# schema.net
KiCad netlist of a schematic drawn in EAGLE
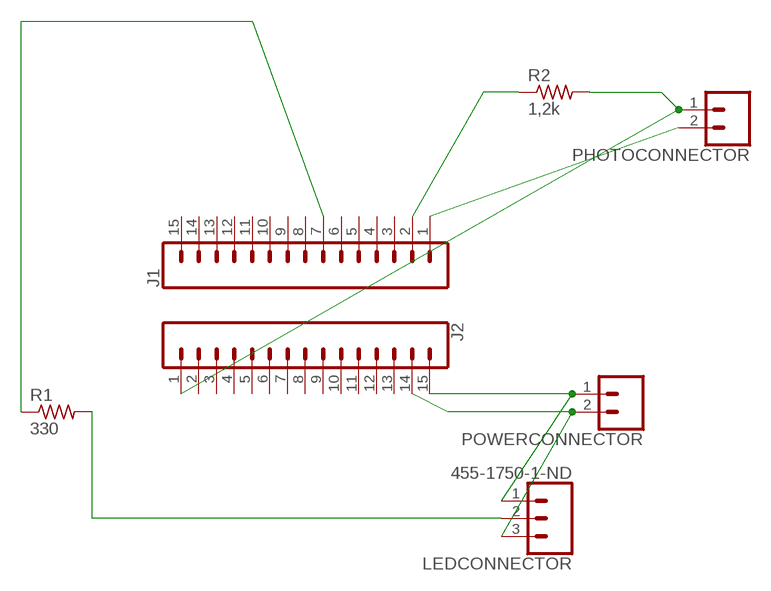
[diagram p0: schematic, sheet 1]

(export (version "E")
  (design (tool "Eeschema 10.0.6"))
  (components
    (comp (ref "J1")
      (value "CONN_15")
      (footprint "eagle-import:1X15")
      (libsource (lib "eagle-import") (part "CONN_15"))
    )
    (comp (ref "J2")
      (value "CONN_15")
      (footprint "eagle-import:1X15")
      (libsource (lib "eagle-import") (part "CONN_15"))
    )
    (comp (ref "LEDCONNECTOR")
      (value "455-1750-1-ND")
      (footprint "eagle-import:1X03")
      (libsource (lib "eagle-import") (part "CONN_03"))
    )
    (comp (ref "PHOTOCONNECTOR")
      (value "CONN_02")
      (footprint "eagle-import:1X02")
      (libsource (lib "eagle-import") (part "CONN_02"))
    )
    (comp (ref "POWERCONNECTOR")
      (value "CONN_02")
      (footprint "eagle-import:1X02")
      (libsource (lib "eagle-import") (part "CONN_02"))
    )
    (comp (ref "R1")
      (value "330")
      (footprint "eagle-import:0204V")
      (libsource (lib "eagle-import") (part "R-US_0204/2V"))
    )
    (comp (ref "R2")
      (value "1,2k")
      (footprint "eagle-import:0204V")
      (libsource (lib "eagle-import") (part "R-US_0204/2V"))
    )
  )
  (nets
    (net (code "1") (name "Net-(J1-Pad1)") (class "Default")
      (node (ref "J1") (pin "1") (pinfunction "1_1") (pintype "passive"))
      (node (ref "PHOTOCONNECTOR") (pin "2") (pinfunction "2_2") (pintype "passive"))
    )
    (net (code "2") (name "Net-(J1-Pad2)") (class "Default")
      (node (ref "J1") (pin "2") (pinfunction "2_2") (pintype "passive"))
      (node (ref "R2") (pin "1") (pinfunction "1_1") (pintype "passive"))
    )
    (net (code "3") (name "Net-(J1-Pad7)") (class "Default")
      (node (ref "J1") (pin "7") (pinfunction "7_7") (pintype "passive"))
      (node (ref "R1") (pin "1") (pinfunction "1_1") (pintype "passive"))
    )
    (net (code "4") (name "Net-(J2-Pad1)") (class "Default")
      (node (ref "J2") (pin "1") (pinfunction "1_1") (pintype "passive"))
      (node (ref "PHOTOCONNECTOR") (pin "1") (pinfunction "1_1") (pintype "passive"))
      (node (ref "R2") (pin "2") (pinfunction "2_2") (pintype "passive"))
    )
    (net (code "5") (name "Net-(J2-Pad14)") (class "Default")
      (node (ref "J2") (pin "14") (pinfunction "14_14") (pintype "passive"))
      (node (ref "LEDCONNECTOR") (pin "3") (pinfunction "3_3") (pintype "passive"))
      (node (ref "POWERCONNECTOR") (pin "2") (pinfunction "2_2") (pintype "passive"))
    )
    (net (code "6") (name "Net-(J2-Pad15)") (class "Default")
      (node (ref "J2") (pin "15") (pinfunction "15_15") (pintype "passive"))
      (node (ref "LEDCONNECTOR") (pin "1") (pinfunction "1_1") (pintype "passive"))
      (node (ref "POWERCONNECTOR") (pin "1") (pinfunction "1_1") (pintype "passive"))
    )
    (net (code "7") (name "Net-(LEDCONNECTOR-Pad2)") (class "Default")
      (node (ref "LEDCONNECTOR") (pin "2") (pinfunction "2_2") (pintype "passive"))
      (node (ref "R1") (pin "2") (pinfunction "2_2") (pintype "passive"))
    )
    (net (code "8") (name "unconnected-(J1-Pad3)") (class "Default")
      (node (ref "J1") (pin "3") (pinfunction "3_3") (pintype "passive"))
    )
    (net (code "9") (name "unconnected-(J1-Pad4)") (class "Default")
      (node (ref "J1") (pin "4") (pinfunction "4_4") (pintype "passive"))
    )
    (net (code "10") (name "unconnected-(J1-Pad5)") (class "Default")
      (node (ref "J1") (pin "5") (pinfunction "5_5") (pintype "passive"))
    )
    (net (code "11") (name "unconnected-(J1-Pad6)") (class "Default")
      (node (ref "J1") (pin "6") (pinfunction "6_6") (pintype "passive"))
    )
    (net (code "12") (name "unconnected-(J1-Pad8)") (class "Default")
      (node (ref "J1") (pin "8") (pinfunction "8_8") (pintype "passive"))
    )
    (net (code "13") (name "unconnected-(J1-Pad9)") (class "Default")
      (node (ref "J1") (pin "9") (pinfunction "9_9") (pintype "passive"))
    )
    (net (code "14") (name "unconnected-(J1-Pad10)") (class "Default")
      (node (ref "J1") (pin "10") (pinfunction "10_10") (pintype "passive"))
    )
    (net (code "15") (name "unconnected-(J1-Pad11)") (class "Default")
      (node (ref "J1") (pin "11") (pinfunction "11_11") (pintype "passive"))
    )
    (net (code "16") (name "unconnected-(J1-Pad12)") (class "Default")
      (node (ref "J1") (pin "12") (pinfunction "12_12") (pintype "passive"))
    )
    (net (code "17") (name "unconnected-(J1-Pad13)") (class "Default")
      (node (ref "J1") (pin "13") (pinfunction "13_13") (pintype "passive"))
    )
    (net (code "18") (name "unconnected-(J1-Pad14)") (class "Default")
      (node (ref "J1") (pin "14") (pinfunction "14_14") (pintype "passive"))
    )
    (net (code "19") (name "unconnected-(J1-Pad15)") (class "Default")
      (node (ref "J1") (pin "15") (pinfunction "15_15") (pintype "passive"))
    )
    (net (code "20") (name "unconnected-(J2-Pad2)") (class "Default")
      (node (ref "J2") (pin "2") (pinfunction "2_2") (pintype "passive"))
    )
    (net (code "21") (name "unconnected-(J2-Pad3)") (class "Default")
      (node (ref "J2") (pin "3") (pinfunction "3_3") (pintype "passive"))
    )
    (net (code "22") (name "unconnected-(J2-Pad4)") (class "Default")
      (node (ref "J2") (pin "4") (pinfunction "4_4") (pintype "passive"))
    )
    (net (code "23") (name "unconnected-(J2-Pad5)") (class "Default")
      (node (ref "J2") (pin "5") (pinfunction "5_5") (pintype "passive"))
    )
    (net (code "24") (name "unconnected-(J2-Pad6)") (class "Default")
      (node (ref "J2") (pin "6") (pinfunction "6_6") (pintype "passive"))
    )
    (net (code "25") (name "unconnected-(J2-Pad7)") (class "Default")
      (node (ref "J2") (pin "7") (pinfunction "7_7") (pintype "passive"))
    )
    (net (code "26") (name "unconnected-(J2-Pad8)") (class "Default")
      (node (ref "J2") (pin "8") (pinfunction "8_8") (pintype "passive"))
    )
    (net (code "27") (name "unconnected-(J2-Pad9)") (class "Default")
      (node (ref "J2") (pin "9") (pinfunction "9_9") (pintype "passive"))
    )
    (net (code "28") (name "unconnected-(J2-Pad10)") (class "Default")
      (node (ref "J2") (pin "10") (pinfunction "10_10") (pintype "passive"))
    )
    (net (code "29") (name "unconnected-(J2-Pad11)") (class "Default")
      (node (ref "J2") (pin "11") (pinfunction "11_11") (pintype "passive"))
    )
    (net (code "30") (name "unconnected-(J2-Pad12)") (class "Default")
      (node (ref "J2") (pin "12") (pinfunction "12_12") (pintype "passive"))
    )
    (net (code "31") (name "unconnected-(J2-Pad13)") (class "Default")
      (node (ref "J2") (pin "13") (pinfunction "13_13") (pintype "passive"))
    )
  )
)
